# mini-v1_1.net
KiCad netlist of a schematic drawn in EAGLE
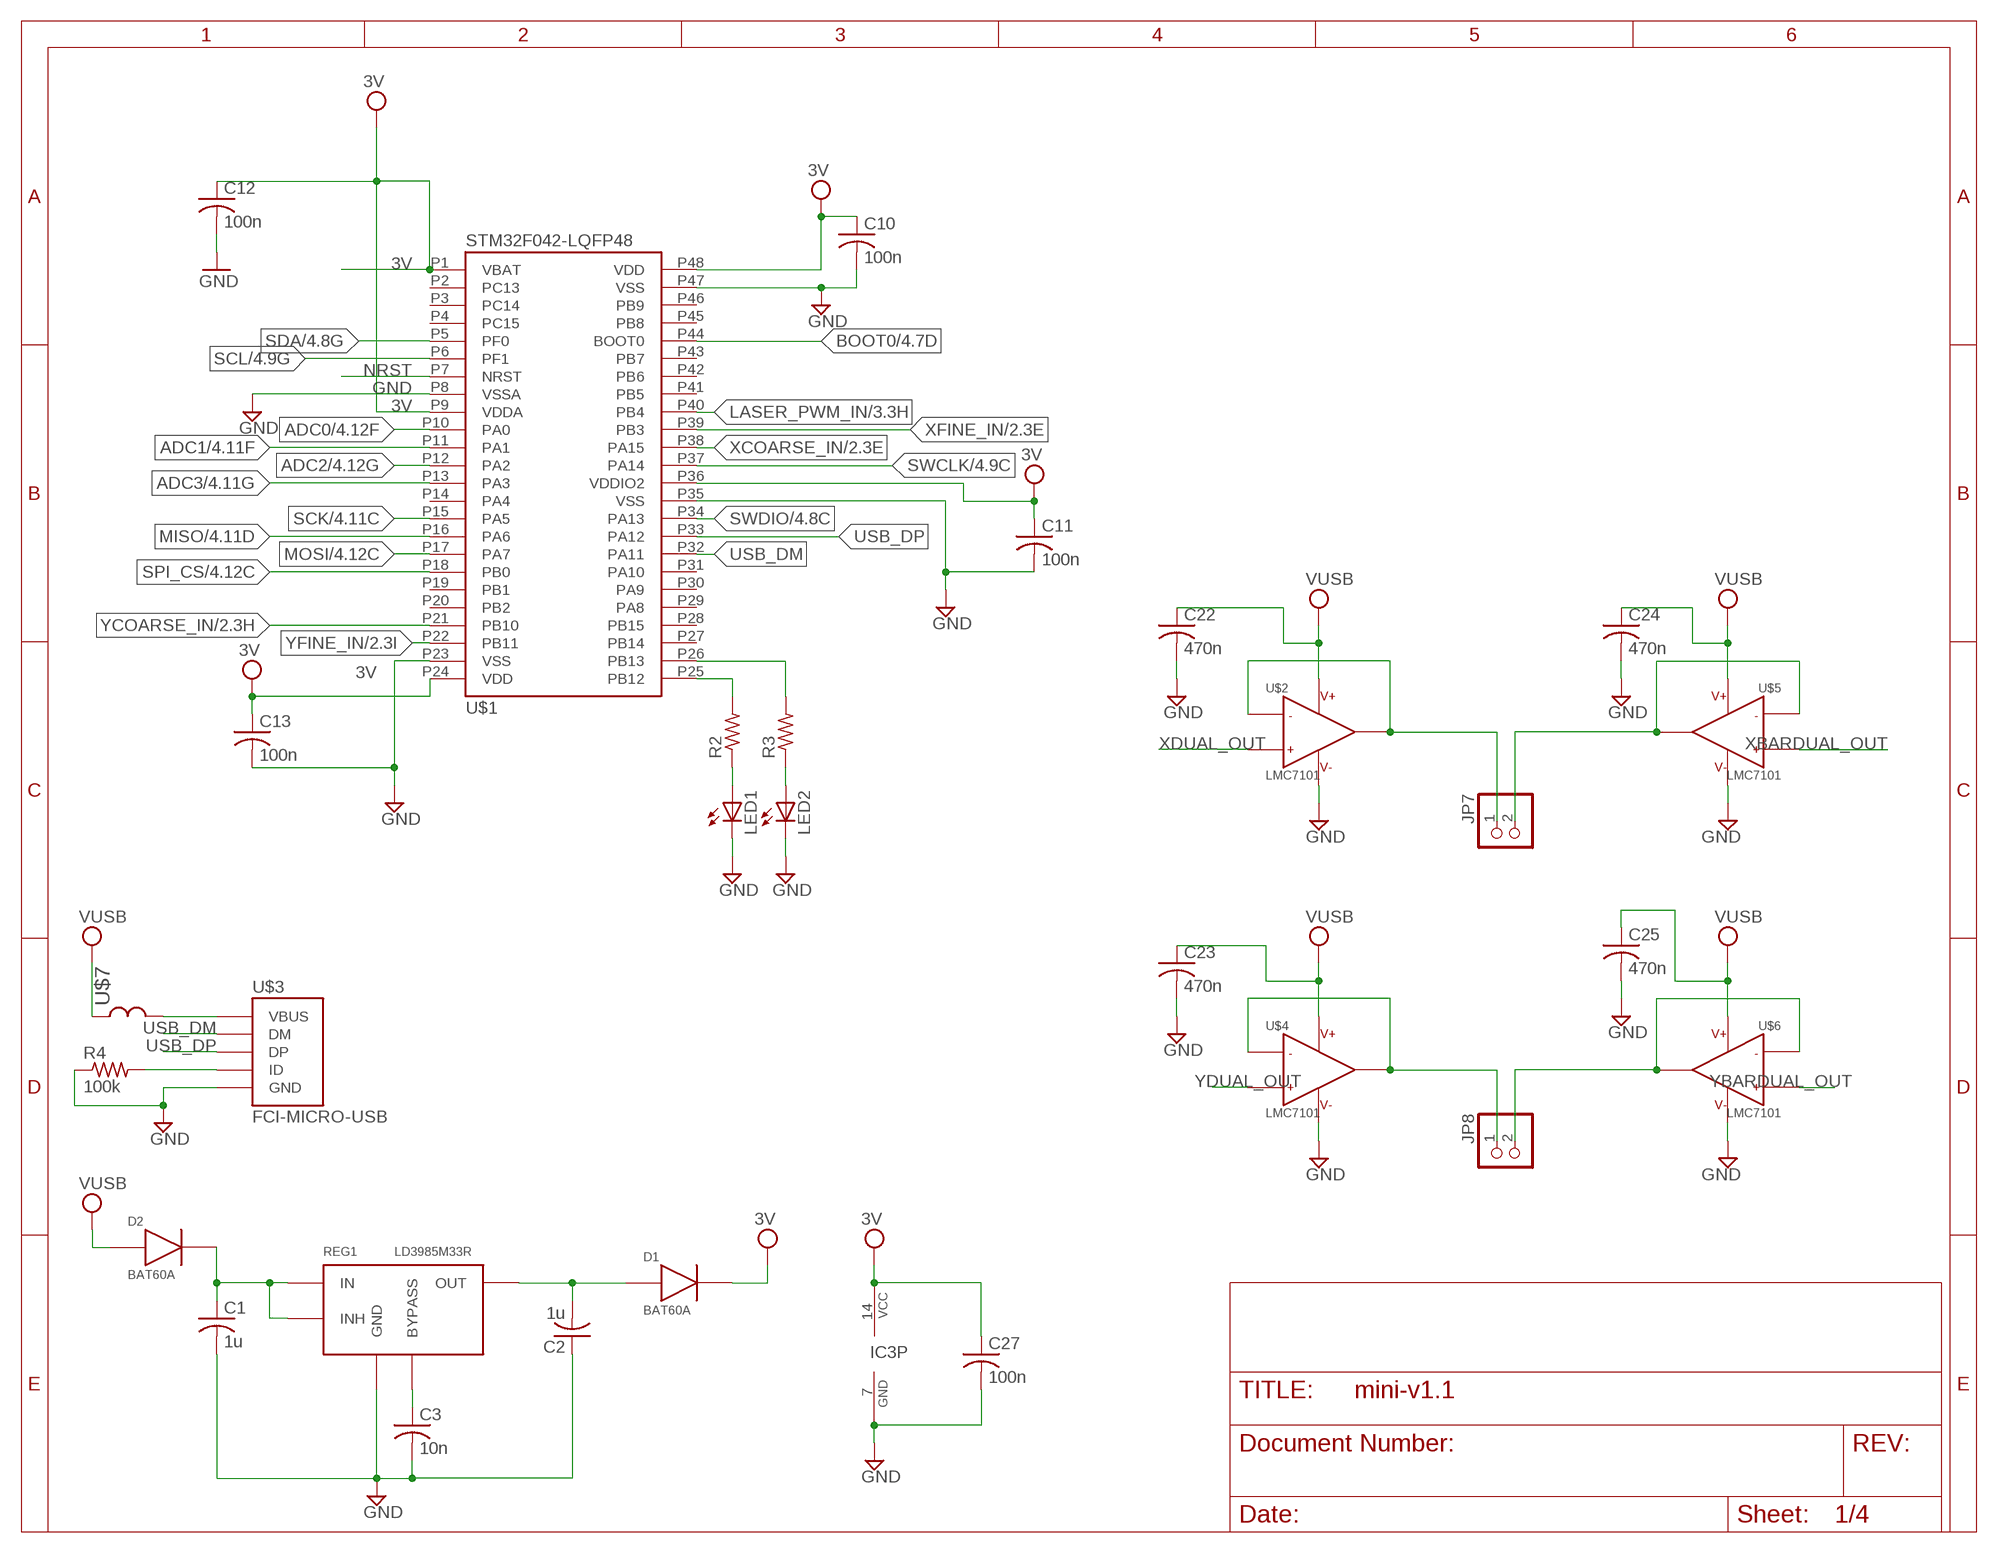
[diagram p0: schematic, sheet 1]
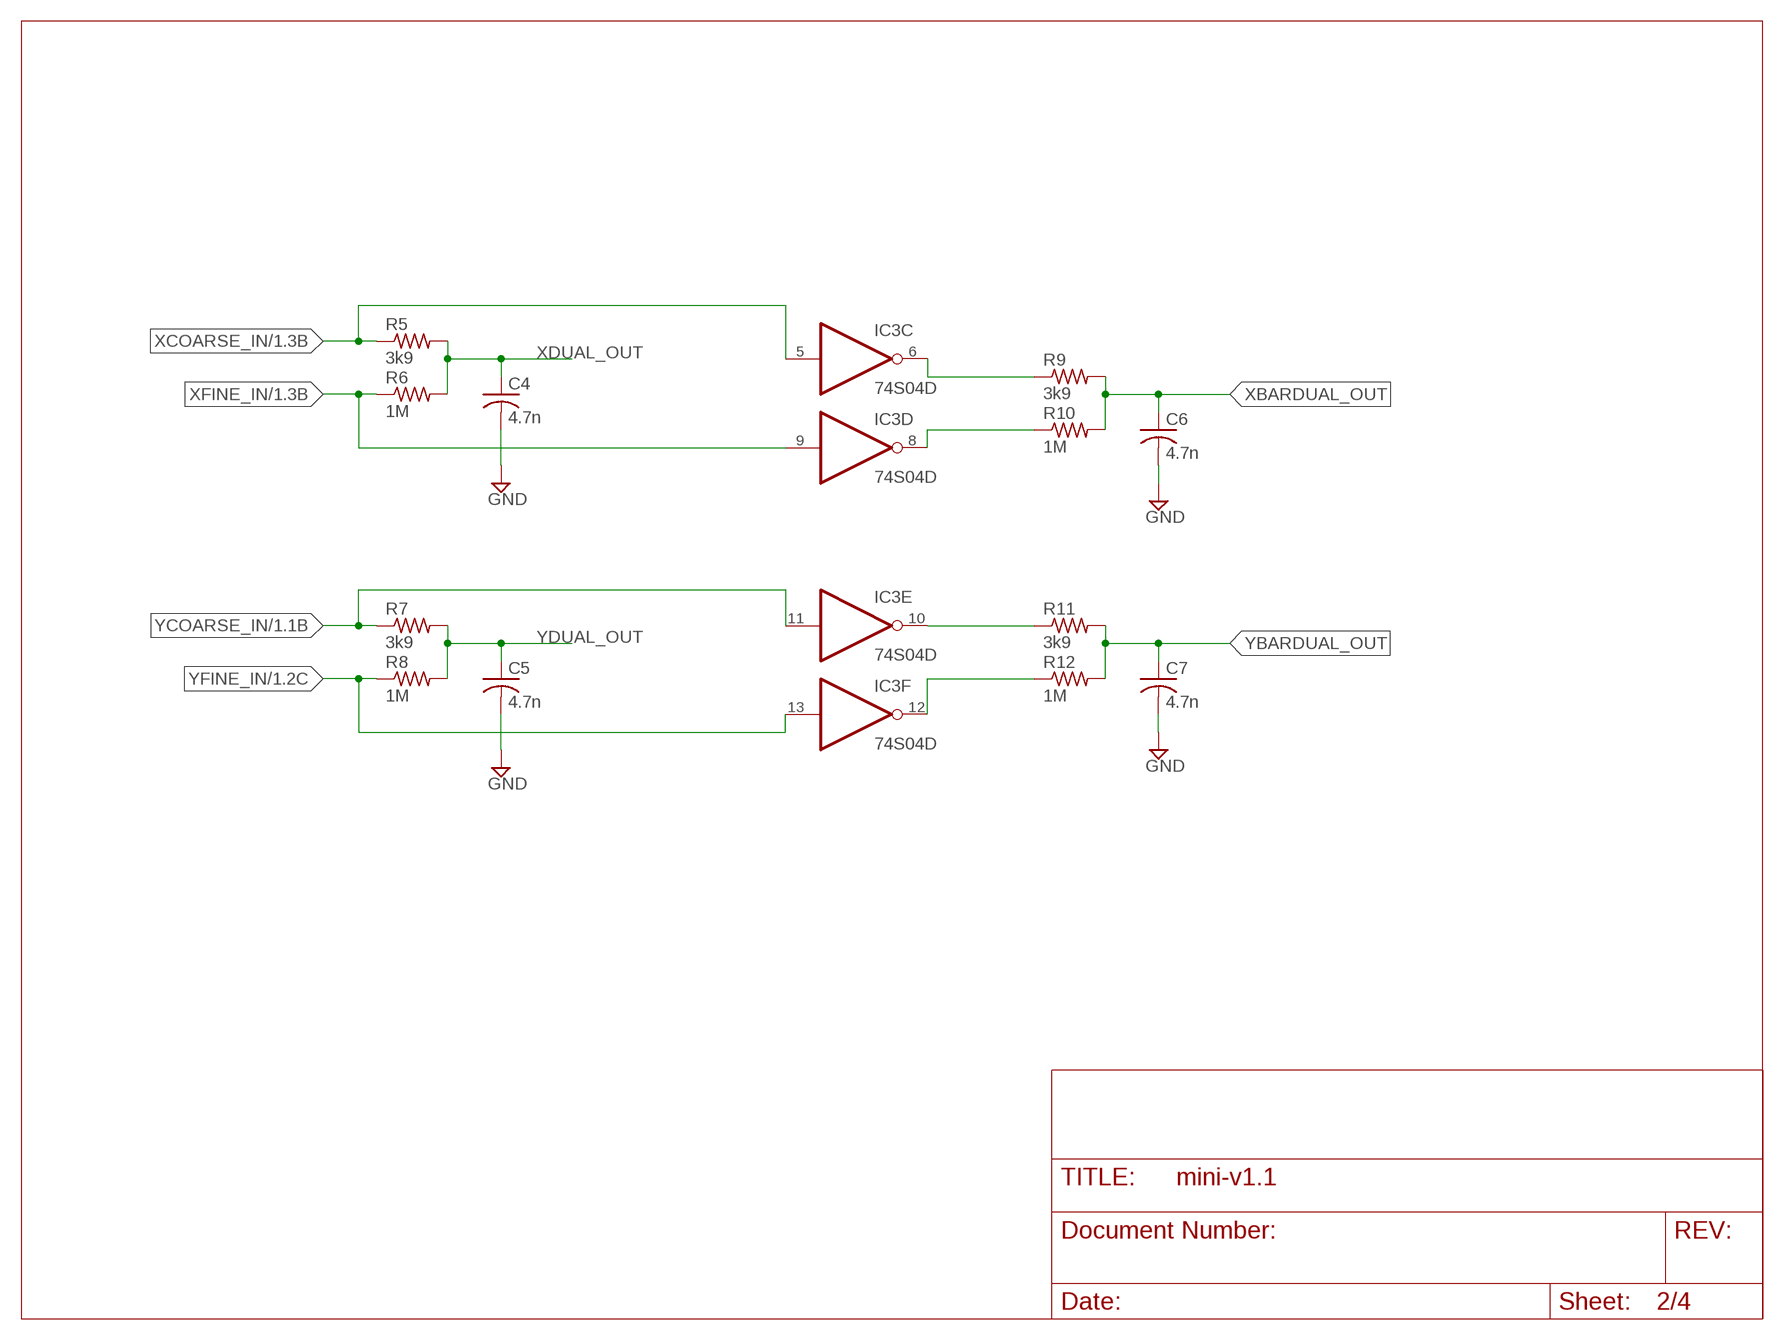
[diagram p1: schematic, sheet 2]
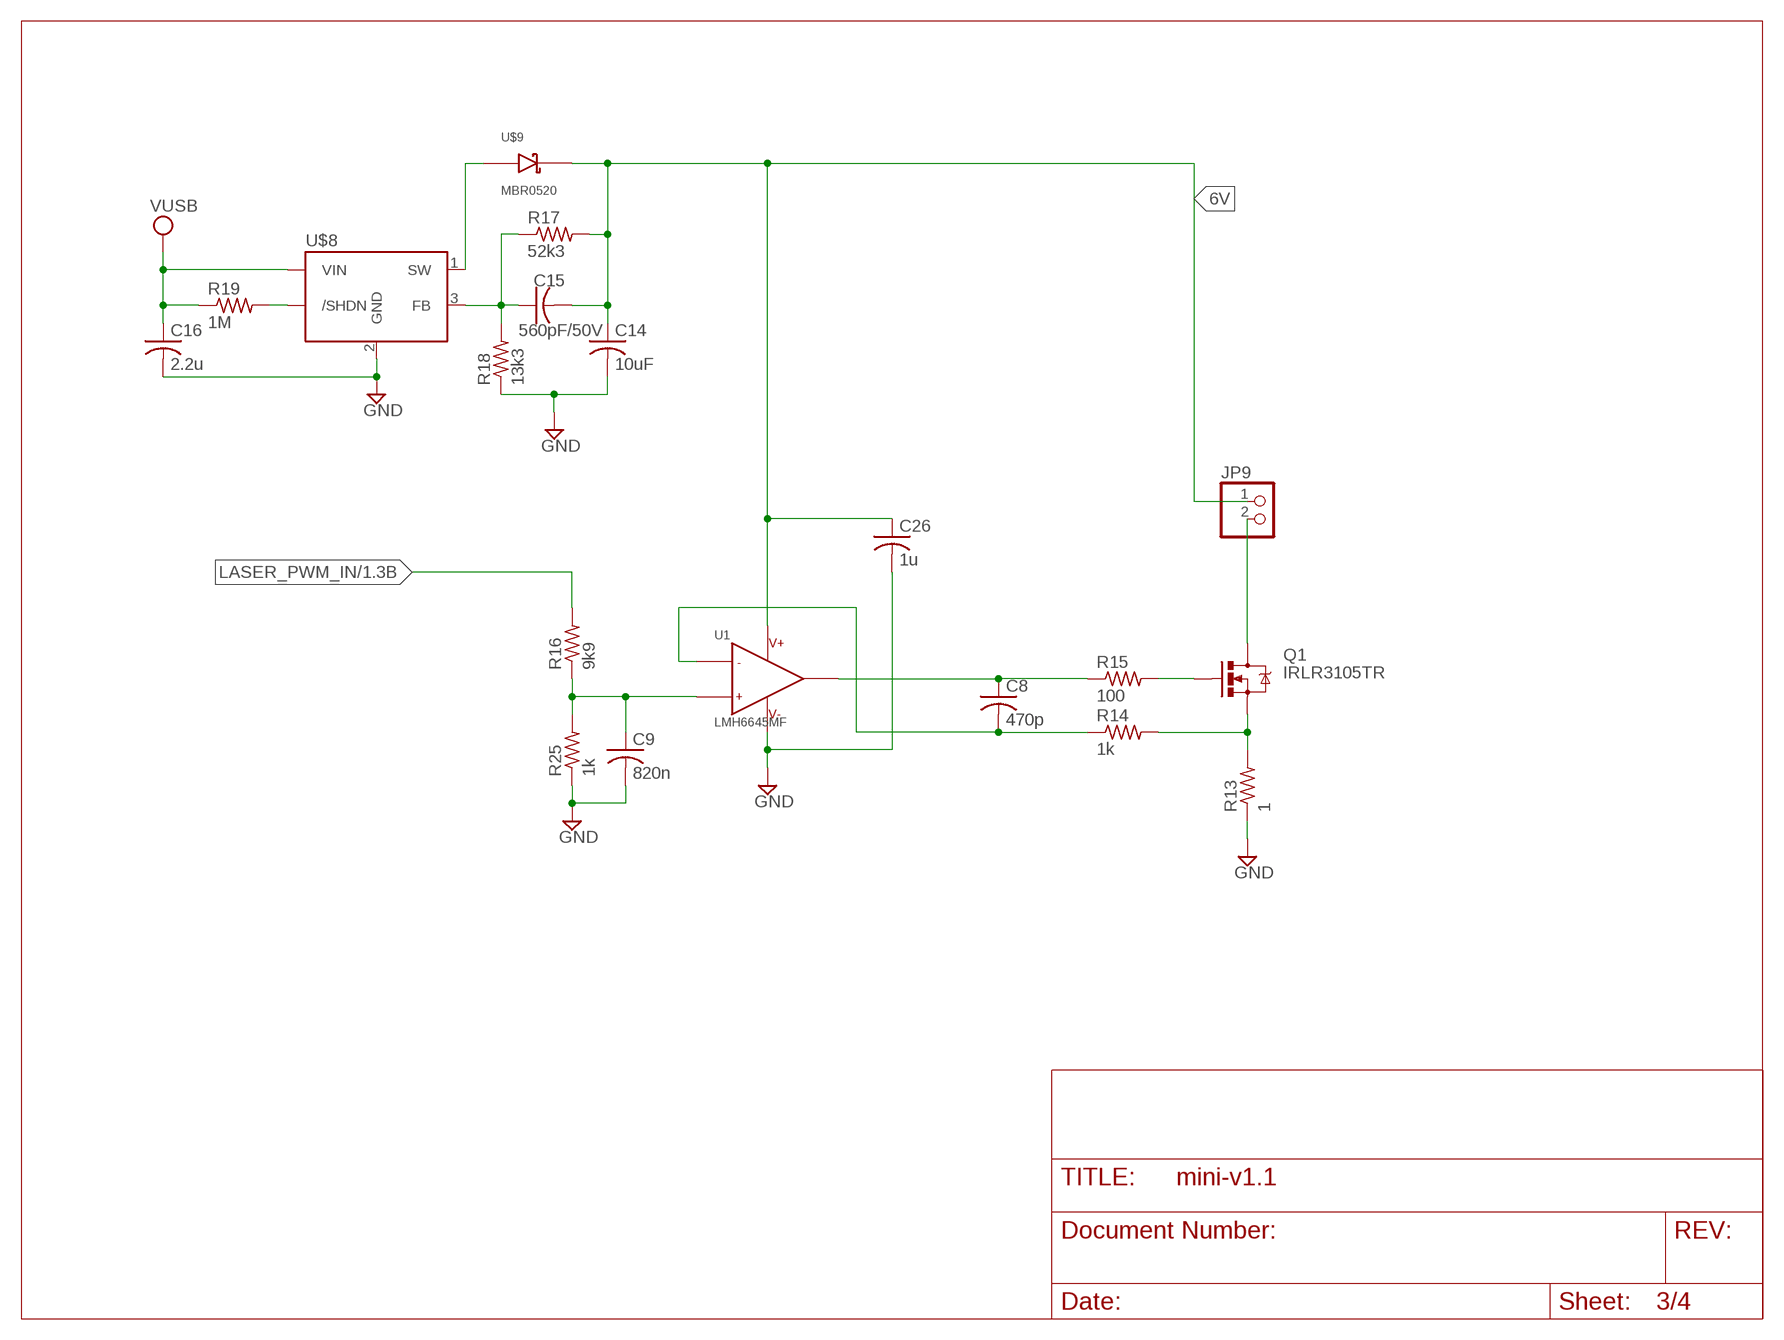
[diagram p2: schematic, sheet 3]
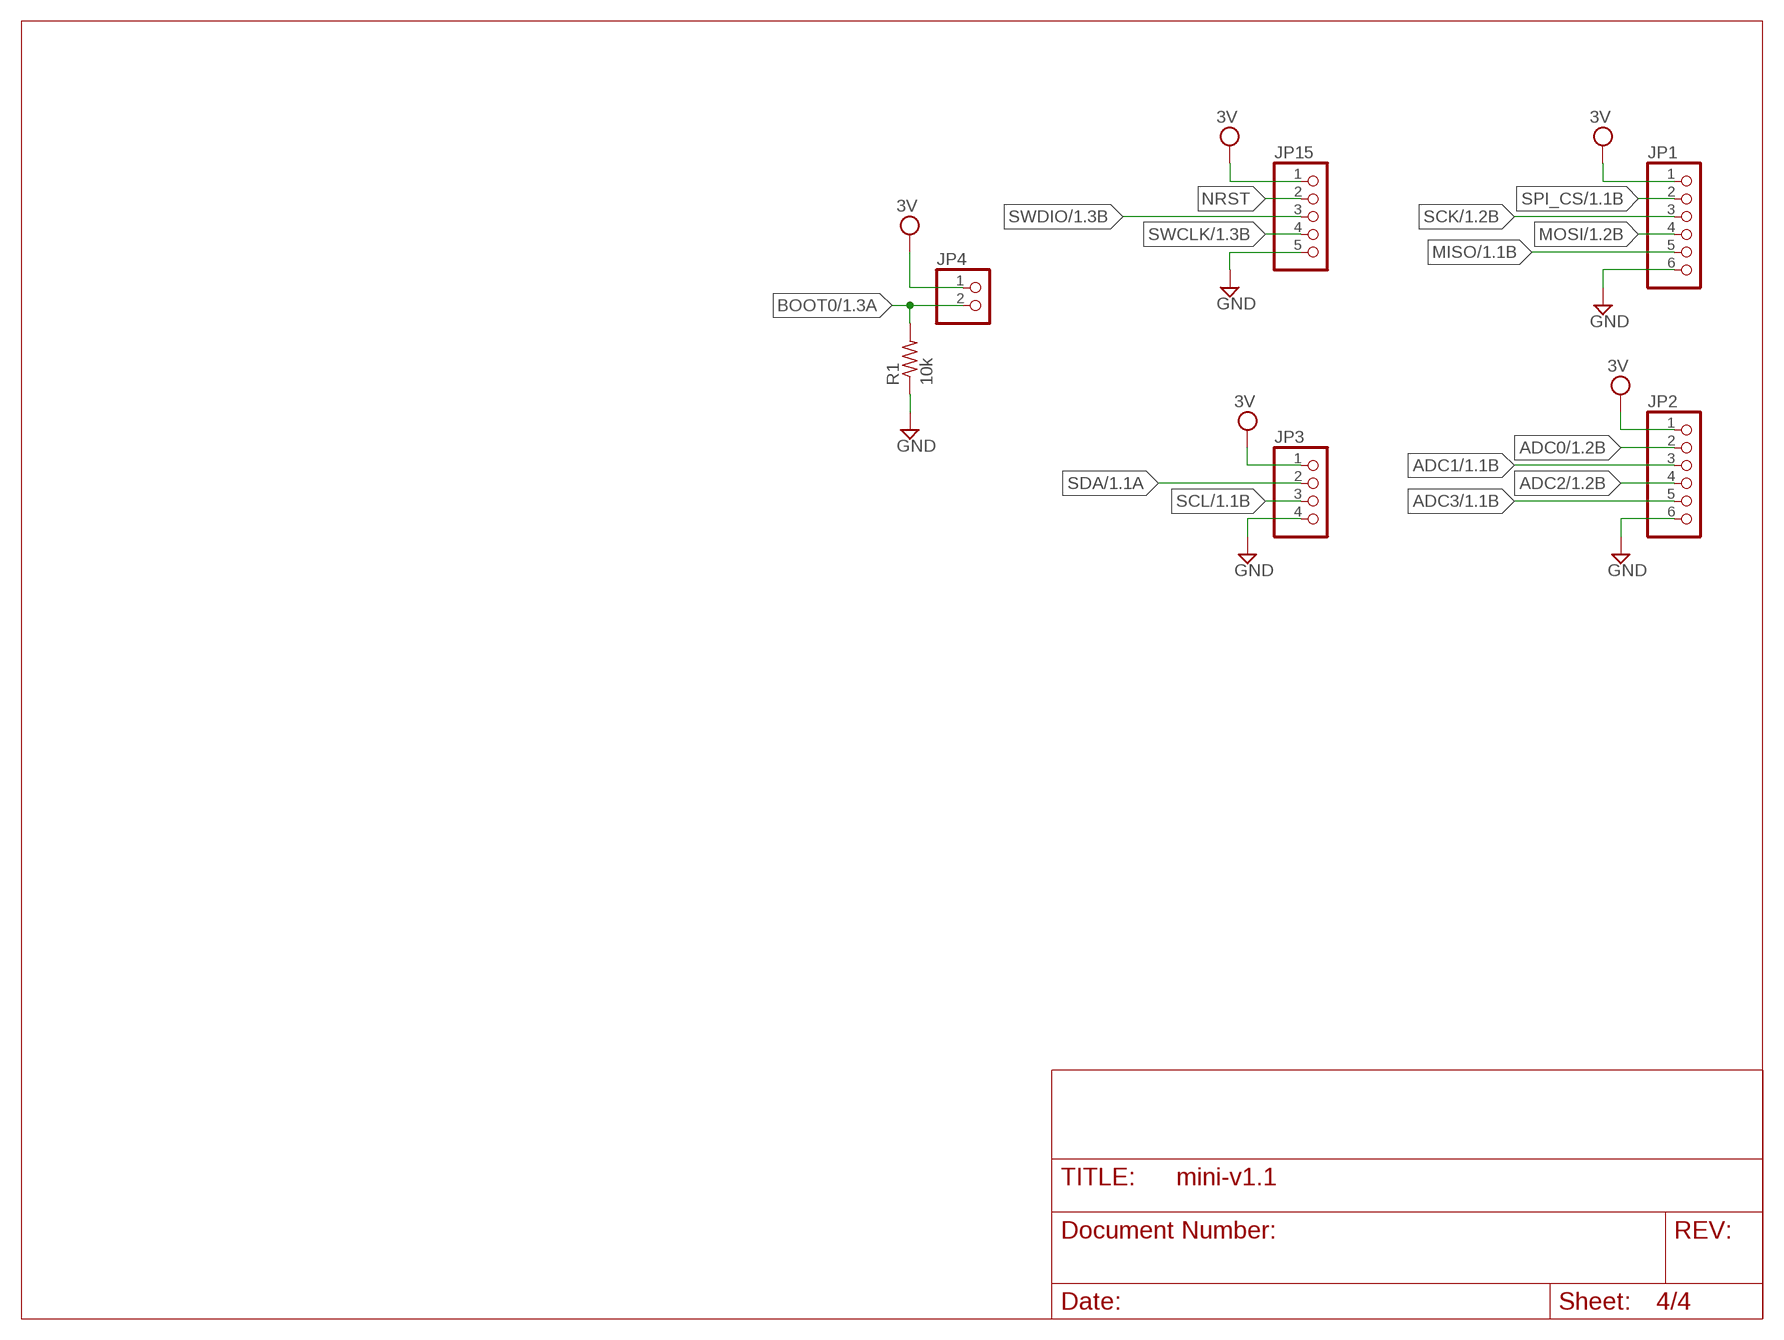
[diagram p3: schematic, sheet 4]

(export (version "E")
  (design (tool "Eeschema 10.0.6"))
  (components
    (comp (ref "C8")
      (value "470p")
      (footprint "eagle-import:C0603")
      (libsource (lib "eagle-import") (part "C-USC0603"))
    )
    (comp (ref "C9")
      (value "820n")
      (footprint "eagle-import:C0603")
      (libsource (lib "eagle-import") (part "C-USC0603"))
    )
    (comp (ref "C14")
      (value "10uF")
      (footprint "eagle-import:C0603")
      (libsource (lib "eagle-import") (part "C-USC0603"))
    )
    (comp (ref "C15")
      (value "560pF/50V")
      (footprint "eagle-import:C0603")
      (libsource (lib "eagle-import") (part "C-USC0603"))
    )
    (comp (ref "C16")
      (value "2.2u")
      (footprint "eagle-import:C0603")
      (libsource (lib "eagle-import") (part "C-USC0603"))
    )
    (comp (ref "C26")
      (value "1u")
      (footprint "eagle-import:C0603")
      (libsource (lib "eagle-import") (part "C-USC0603"))
    )
    (comp (ref "JP9")
      (value "PINHD-1X2")
      (footprint "eagle-import:1X02")
      (libsource (lib "eagle-import") (part "PINHD-1X2"))
    )
    (comp (ref "Q1")
      (value "IRLR3105TR")
      (footprint "eagle-import:DPAK")
      (libsource (lib "eagle-import") (part "FET-N-IRLR3105TRIRLR3105TR"))
    )
    (comp (ref "R13")
      (value "1")
      (footprint "eagle-import:R0603")
      (libsource (lib "eagle-import") (part "R-US_R0603"))
    )
    (comp (ref "R14")
      (value "1k")
      (footprint "eagle-import:R0603")
      (libsource (lib "eagle-import") (part "R-US_R0603"))
    )
    (comp (ref "R15")
      (value "100")
      (footprint "eagle-import:R0603")
      (libsource (lib "eagle-import") (part "R-US_R0603"))
    )
    (comp (ref "R16")
      (value "9k9")
      (footprint "eagle-import:R0603")
      (libsource (lib "eagle-import") (part "R-US_R0603"))
    )
    (comp (ref "R17")
      (value "52k3")
      (footprint "eagle-import:R0603")
      (libsource (lib "eagle-import") (part "R-US_R0603"))
    )
    (comp (ref "R18")
      (value "13k3")
      (footprint "eagle-import:R0603")
      (libsource (lib "eagle-import") (part "R-US_R0603"))
    )
    (comp (ref "R19")
      (value "1M")
      (footprint "eagle-import:R0603")
      (libsource (lib "eagle-import") (part "R-US_R0603"))
    )
    (comp (ref "R25")
      (value "1k")
      (footprint "eagle-import:R0603")
      (libsource (lib "eagle-import") (part "R-US_R0603"))
    )
    (comp (ref "U$8")
      (value "LMR62014")
      (footprint "eagle-import:SOT23-5")
      (libsource (lib "eagle-import") (part "LMR62014"))
    )
    (comp (ref "U$9")
      (value "MBR0520")
      (footprint "eagle-import:SOD123")
      (libsource (lib "eagle-import") (part "MBR0520"))
    )
    (comp (ref "U1")
      (value "LMH6645MF")
      (footprint "eagle-import:SOT23-5")
      (libsource (lib "eagle-import") (part "OPAMP-SINGLELMH6645MF"))
    )
    (comp (ref "JP1")
      (value "PINHD-1X6")
      (footprint "eagle-import:1X06")
      (libsource (lib "eagle-import") (part "PINHD-1X6"))
    )
    (comp (ref "JP2")
      (value "PINHD-1X6")
      (footprint "eagle-import:1X06")
      (libsource (lib "eagle-import") (part "PINHD-1X6"))
    )
    (comp (ref "JP3")
      (value "PINHD-1X4")
      (footprint "eagle-import:1X04")
      (libsource (lib "eagle-import") (part "PINHD-1X4"))
    )
    (comp (ref "JP4")
      (value "PINHD-1X2")
      (footprint "eagle-import:1X02")
      (libsource (lib "eagle-import") (part "PINHD-1X2"))
    )
    (comp (ref "JP15")
      (value "PINHD-1X5")
      (footprint "eagle-import:1X05")
      (libsource (lib "eagle-import") (part "PINHD-1X5"))
    )
    (comp (ref "R1")
      (value "10k")
      (footprint "eagle-import:R0603")
      (libsource (lib "eagle-import") (part "R-US_R0603"))
    )
    (comp (ref "C4")
      (value "4.7n")
      (footprint "eagle-import:C0603")
      (libsource (lib "eagle-import") (part "C-USC0603"))
    )
    (comp (ref "C5")
      (value "4.7n")
      (footprint "eagle-import:C0603")
      (libsource (lib "eagle-import") (part "C-USC0603"))
    )
    (comp (ref "C6")
      (value "4.7n")
      (footprint "eagle-import:C0603")
      (libsource (lib "eagle-import") (part "C-USC0603"))
    )
    (comp (ref "C7")
      (value "4.7n")
      (footprint "eagle-import:C0603")
      (libsource (lib "eagle-import") (part "C-USC0603"))
    )
    (comp (ref "IC3")
      (value "74S04D")
      (footprint "eagle-import:SO14")
      (libsource (lib "eagle-import") (part "7404DS"))
    )
    (comp (ref "R5")
      (value "3k9")
      (footprint "eagle-import:R0603")
      (libsource (lib "eagle-import") (part "R-US_R0603"))
    )
    (comp (ref "R6")
      (value "1M")
      (footprint "eagle-import:R0603")
      (libsource (lib "eagle-import") (part "R-US_R0603"))
    )
    (comp (ref "R7")
      (value "3k9")
      (footprint "eagle-import:R0603")
      (libsource (lib "eagle-import") (part "R-US_R0603"))
    )
    (comp (ref "R8")
      (value "1M")
      (footprint "eagle-import:R0603")
      (libsource (lib "eagle-import") (part "R-US_R0603"))
    )
    (comp (ref "R9")
      (value "3k9")
      (footprint "eagle-import:R0603")
      (libsource (lib "eagle-import") (part "R-US_R0603"))
    )
    (comp (ref "R10")
      (value "1M")
      (footprint "eagle-import:R0603")
      (libsource (lib "eagle-import") (part "R-US_R0603"))
    )
    (comp (ref "R11")
      (value "3k9")
      (footprint "eagle-import:R0603")
      (libsource (lib "eagle-import") (part "R-US_R0603"))
    )
    (comp (ref "R12")
      (value "1M")
      (footprint "eagle-import:R0603")
      (libsource (lib "eagle-import") (part "R-US_R0603"))
    )
    (comp (ref "C1")
      (value "1u")
      (footprint "eagle-import:C0603")
      (libsource (lib "eagle-import") (part "C-USC0603"))
    )
    (comp (ref "C2")
      (value "1u")
      (footprint "eagle-import:C0603")
      (libsource (lib "eagle-import") (part "C-USC0603"))
    )
    (comp (ref "C3")
      (value "10n")
      (footprint "eagle-import:C0603")
      (libsource (lib "eagle-import") (part "C-USC0603"))
    )
    (comp (ref "C10")
      (value "100n")
      (footprint "eagle-import:C0603")
      (libsource (lib "eagle-import") (part "C-USC0603"))
    )
    (comp (ref "C11")
      (value "100n")
      (footprint "eagle-import:C0603")
      (libsource (lib "eagle-import") (part "C-USC0603"))
    )
    (comp (ref "C12")
      (value "100n")
      (footprint "eagle-import:C0603")
      (libsource (lib "eagle-import") (part "C-USC0603"))
    )
    (comp (ref "C13")
      (value "100n")
      (footprint "eagle-import:C0603")
      (libsource (lib "eagle-import") (part "C-USC0603"))
    )
    (comp (ref "C22")
      (value "470n")
      (footprint "eagle-import:C0603")
      (libsource (lib "eagle-import") (part "C-USC0603"))
    )
    (comp (ref "C23")
      (value "470n")
      (footprint "eagle-import:C0603")
      (libsource (lib "eagle-import") (part "C-USC0603"))
    )
    (comp (ref "C24")
      (value "470n")
      (footprint "eagle-import:C0603")
      (libsource (lib "eagle-import") (part "C-USC0603"))
    )
    (comp (ref "C25")
      (value "470n")
      (footprint "eagle-import:C0603")
      (libsource (lib "eagle-import") (part "C-USC0603"))
    )
    (comp (ref "C27")
      (value "100n")
      (footprint "eagle-import:C0603")
      (libsource (lib "eagle-import") (part "C-USC0603"))
    )
    (comp (ref "D1")
      (value "BAT60A")
      (footprint "eagle-import:SOD323")
      (libsource (lib "eagle-import") (part "BAT60A"))
    )
    (comp (ref "D2")
      (value "BAT60A")
      (footprint "eagle-import:SOD323")
      (libsource (lib "eagle-import") (part "BAT60A"))
    )
    (comp (ref "JP7")
      (value "PINHD-1X2")
      (footprint "eagle-import:1X02")
      (libsource (lib "eagle-import") (part "PINHD-1X2"))
    )
    (comp (ref "JP8")
      (value "PINHD-1X2")
      (footprint "eagle-import:1X02")
      (libsource (lib "eagle-import") (part "PINHD-1X2"))
    )
    (comp (ref "LED1")
      (value "LED")
      (footprint "eagle-import:SMARTLED-TTW")
      (libsource (lib "eagle-import") (part "LED"))
    )
    (comp (ref "LED2")
      (value "LED")
      (footprint "eagle-import:SMARTLED-TTW")
      (libsource (lib "eagle-import") (part "LED"))
    )
    (comp (ref "R2")
      (value "R-US_R0603")
      (footprint "eagle-import:R0603")
      (libsource (lib "eagle-import") (part "R-US_R0603"))
    )
    (comp (ref "R3")
      (value "R-US_R0603")
      (footprint "eagle-import:R0603")
      (libsource (lib "eagle-import") (part "R-US_R0603"))
    )
    (comp (ref "R4")
      (value "100k")
      (footprint "eagle-import:R0603")
      (libsource (lib "eagle-import") (part "R-US_R0603"))
    )
    (comp (ref "REG1")
      (value "LD3985M33R")
      (footprint "eagle-import:SOT23-5L")
      (libsource (lib "eagle-import") (part "LD3985MXXR"))
    )
    (comp (ref "U$1")
      (value "STM32F042-LQFP48")
      (footprint "eagle-import:LQFP48")
      (libsource (lib "eagle-import") (part "STM32F042-LQFP48"))
    )
    (comp (ref "U$2")
      (value "LMC7101")
      (footprint "eagle-import:SOT23-5")
      (libsource (lib "eagle-import") (part "LMC7101"))
    )
    (comp (ref "U$3")
      (value "FCI-MICRO-USB")
      (footprint "eagle-import:FCI-MICROUSB")
      (libsource (lib "eagle-import") (part "FCI-MICRO-USB"))
    )
    (comp (ref "U$4")
      (value "LMC7101")
      (footprint "eagle-import:SOT23-5")
      (libsource (lib "eagle-import") (part "LMC7101"))
    )
    (comp (ref "U$5")
      (value "LMC7101")
      (footprint "eagle-import:SOT23-5")
      (libsource (lib "eagle-import") (part "LMC7101"))
    )
    (comp (ref "U$6")
      (value "LMC7101")
      (footprint "eagle-import:SOT23-5")
      (libsource (lib "eagle-import") (part "LMC7101"))
    )
    (comp (ref "U$7")
      (value "L_TDK_1005")
      (footprint "eagle-import:MLK1005")
      (libsource (lib "eagle-import") (part "L_TDK_1005"))
    )
  )
  (nets
    (net (code "1") (name "3V") (class "Default")
      (node (ref "C10") (pin "1") (pinfunction "1_1") (pintype "passive"))
      (node (ref "C11") (pin "1") (pinfunction "1_1") (pintype "passive"))
      (node (ref "C12") (pin "1") (pinfunction "1_1") (pintype "passive"))
      (node (ref "C13") (pin "1") (pinfunction "1_1") (pintype "passive"))
      (node (ref "C27") (pin "1") (pinfunction "1_1") (pintype "passive"))
      (node (ref "D1") (pin "1") (pinfunction "1_1") (pintype "bidirectional"))
      (node (ref "IC3") (pin "14") (pinfunction "VCC_14") (pintype "power_in"))
      (node (ref "JP1") (pin "1") (pinfunction "1_1") (pintype "passive"))
      (node (ref "JP15") (pin "1") (pinfunction "1_1") (pintype "passive"))
      (node (ref "JP2") (pin "1") (pinfunction "1_1") (pintype "passive"))
      (node (ref "JP3") (pin "1") (pinfunction "1_1") (pintype "passive"))
      (node (ref "JP4") (pin "1") (pinfunction "1_1") (pintype "passive"))
      (node (ref "U$1") (pin "P1") (pinfunction "VBAT_P1") (pintype "bidirectional"))
      (node (ref "U$1") (pin "P24") (pinfunction "VDD_P24") (pintype "bidirectional"))
      (node (ref "U$1") (pin "P36") (pinfunction "VDDIO2_P36") (pintype "bidirectional"))
      (node (ref "U$1") (pin "P48") (pinfunction "VDD_P48") (pintype "bidirectional"))
      (node (ref "U$1") (pin "P9") (pinfunction "VDDA_P9") (pintype "bidirectional"))
    )
    (net (code "2") (name "6V") (class "Default")
      (node (ref "C14") (pin "1") (pinfunction "1_1") (pintype "passive"))
      (node (ref "C15") (pin "2") (pinfunction "2_2") (pintype "passive"))
      (node (ref "C26") (pin "1") (pinfunction "1_1") (pintype "passive"))
      (node (ref "JP9") (pin "1") (pinfunction "1_1") (pintype "passive"))
      (node (ref "R17") (pin "2") (pinfunction "2_2") (pintype "passive"))
      (node (ref "U$9") (pin "CATHODE") (pinfunction "CATHODE_CATHODE") (pintype "bidirectional"))
      (node (ref "U1") (pin "5") (pinfunction "V+_5") (pintype "power_in"))
    )
    (net (code "3") (name "ADC0") (class "Default")
      (node (ref "JP2") (pin "2") (pinfunction "2_2") (pintype "passive"))
      (node (ref "U$1") (pin "P10") (pinfunction "PA0_P10") (pintype "bidirectional"))
    )
    (net (code "4") (name "ADC1") (class "Default")
      (node (ref "JP2") (pin "3") (pinfunction "3_3") (pintype "passive"))
      (node (ref "U$1") (pin "P11") (pinfunction "PA1_P11") (pintype "bidirectional"))
    )
    (net (code "5") (name "ADC2") (class "Default")
      (node (ref "JP2") (pin "4") (pinfunction "4_4") (pintype "passive"))
      (node (ref "U$1") (pin "P12") (pinfunction "PA2_P12") (pintype "bidirectional"))
    )
    (net (code "6") (name "ADC3") (class "Default")
      (node (ref "JP2") (pin "5") (pinfunction "5_5") (pintype "passive"))
      (node (ref "U$1") (pin "P13") (pinfunction "PA3_P13") (pintype "bidirectional"))
    )
    (net (code "7") (name "BOOT0") (class "Default")
      (node (ref "JP4") (pin "2") (pinfunction "2_2") (pintype "passive"))
      (node (ref "R1") (pin "2") (pinfunction "2_2") (pintype "passive"))
      (node (ref "U$1") (pin "P44") (pinfunction "BOOT0_P44") (pintype "bidirectional"))
    )
    (net (code "8") (name "GND") (class "Default")
      (node (ref "C1") (pin "2") (pinfunction "2_2") (pintype "passive"))
      (node (ref "C10") (pin "2") (pinfunction "2_2") (pintype "passive"))
      (node (ref "C11") (pin "2") (pinfunction "2_2") (pintype "passive"))
      (node (ref "C12") (pin "2") (pinfunction "2_2") (pintype "passive"))
      (node (ref "C13") (pin "2") (pinfunction "2_2") (pintype "passive"))
      (node (ref "C14") (pin "2") (pinfunction "2_2") (pintype "passive"))
      (node (ref "C16") (pin "2") (pinfunction "2_2") (pintype "passive"))
      (node (ref "C2") (pin "1") (pinfunction "1_1") (pintype "passive"))
      (node (ref "C22") (pin "2") (pinfunction "2_2") (pintype "passive"))
      (node (ref "C23") (pin "2") (pinfunction "2_2") (pintype "passive"))
      (node (ref "C24") (pin "2") (pinfunction "2_2") (pintype "passive"))
      (node (ref "C25") (pin "2") (pinfunction "2_2") (pintype "passive"))
      (node (ref "C26") (pin "2") (pinfunction "2_2") (pintype "passive"))
      (node (ref "C27") (pin "2") (pinfunction "2_2") (pintype "passive"))
      (node (ref "C3") (pin "2") (pinfunction "2_2") (pintype "passive"))
      (node (ref "C4") (pin "2") (pinfunction "2_2") (pintype "passive"))
      (node (ref "C5") (pin "2") (pinfunction "2_2") (pintype "passive"))
      (node (ref "C6") (pin "2") (pinfunction "2_2") (pintype "passive"))
      (node (ref "C7") (pin "2") (pinfunction "2_2") (pintype "passive"))
      (node (ref "C9") (pin "2") (pinfunction "2_2") (pintype "passive"))
      (node (ref "IC3") (pin "7") (pinfunction "GND_7") (pintype "power_in"))
      (node (ref "JP1") (pin "6") (pinfunction "6_6") (pintype "passive"))
      (node (ref "JP15") (pin "5") (pinfunction "5_5") (pintype "passive"))
      (node (ref "JP2") (pin "6") (pinfunction "6_6") (pintype "passive"))
      (node (ref "JP3") (pin "4") (pinfunction "4_4") (pintype "passive"))
      (node (ref "LED1") (pin "C@1") (pinfunction "C_C@1") (pintype "passive"))
      (node (ref "LED2") (pin "C@1") (pinfunction "C_C@1") (pintype "passive"))
      (node (ref "R1") (pin "1") (pinfunction "1_1") (pintype "passive"))
      (node (ref "R13") (pin "1") (pinfunction "1_1") (pintype "passive"))
      (node (ref "R18") (pin "1") (pinfunction "1_1") (pintype "passive"))
      (node (ref "R25") (pin "1") (pinfunction "1_1") (pintype "passive"))
      (node (ref "R4") (pin "1") (pinfunction "1_1") (pintype "passive"))
      (node (ref "REG1") (pin "GND") (pinfunction "GND_GND") (pintype "bidirectional"))
      (node (ref "U$1") (pin "P23") (pinfunction "VSS_P23") (pintype "bidirectional"))
      (node (ref "U$1") (pin "P35") (pinfunction "VSS_P35") (pintype "bidirectional"))
      (node (ref "U$1") (pin "P47") (pinfunction "VSS_P47") (pintype "bidirectional"))
      (node (ref "U$1") (pin "P8") (pinfunction "VSSA_P8") (pintype "bidirectional"))
      (node (ref "U$2") (pin "5") (pinfunction "P5_5") (pintype "power_in"))
      (node (ref "U$3") (pin "P5") (pinfunction "GND_P5") (pintype "bidirectional"))
      (node (ref "U$4") (pin "5") (pinfunction "P5_5") (pintype "power_in"))
      (node (ref "U$5") (pin "5") (pinfunction "P5_5") (pintype "power_in"))
      (node (ref "U$6") (pin "5") (pinfunction "P5_5") (pintype "power_in"))
      (node (ref "U$8") (pin "2") (pinfunction "GND_2") (pintype "bidirectional"))
      (node (ref "U1") (pin "2") (pinfunction "V-_2") (pintype "power_in"))
    )
    (net (code "9") (name "LASER_PWM_IN") (class "Default")
      (node (ref "R16") (pin "2") (pinfunction "2_2") (pintype "passive"))
      (node (ref "U$1") (pin "P40") (pinfunction "PB4_P40") (pintype "bidirectional"))
    )
    (net (code "10") (name "MISO") (class "Default")
      (node (ref "JP1") (pin "5") (pinfunction "5_5") (pintype "passive"))
      (node (ref "U$1") (pin "P16") (pinfunction "PA6_P16") (pintype "bidirectional"))
    )
    (net (code "11") (name "MOSI") (class "Default")
      (node (ref "JP1") (pin "4") (pinfunction "4_4") (pintype "passive"))
      (node (ref "U$1") (pin "P17") (pinfunction "PA7_P17") (pintype "bidirectional"))
    )
    (net (code "12") (name "NRST") (class "Default")
      (node (ref "JP15") (pin "2") (pinfunction "2_2") (pintype "passive"))
      (node (ref "U$1") (pin "P7") (pinfunction "NRST_P7") (pintype "bidirectional"))
    )
    (net (code "13") (name "Net-(C2-Pad2)") (class "Default")
      (node (ref "C2") (pin "2") (pinfunction "2_2") (pintype "passive"))
      (node (ref "D1") (pin "2") (pinfunction "2_2") (pintype "bidirectional"))
      (node (ref "REG1") (pin "OUT") (pinfunction "OUT_OUT") (pintype "bidirectional"))
    )
    (net (code "14") (name "Net-(C3-Pad1)") (class "Default")
      (node (ref "C3") (pin "1") (pinfunction "1_1") (pintype "passive"))
      (node (ref "REG1") (pin "BYPASS") (pinfunction "BYPASS_BYPASS") (pintype "bidirectional"))
    )
    (net (code "15") (name "Net-(IC3C-O)") (class "Default")
      (node (ref "IC3") (pin "6") (pinfunction "O_6") (pintype "output"))
      (node (ref "R9") (pin "1") (pinfunction "1_1") (pintype "passive"))
    )
    (net (code "16") (name "Net-(IC3D-O)") (class "Default")
      (node (ref "IC3") (pin "8") (pinfunction "O_8") (pintype "output"))
      (node (ref "R10") (pin "1") (pinfunction "1_1") (pintype "passive"))
    )
    (net (code "17") (name "Net-(IC3E-O)") (class "Default")
      (node (ref "IC3") (pin "10") (pinfunction "O_10") (pintype "output"))
      (node (ref "R11") (pin "1") (pinfunction "1_1") (pintype "passive"))
    )
    (net (code "18") (name "Net-(IC3F-O)") (class "Default")
      (node (ref "IC3") (pin "12") (pinfunction "O_12") (pintype "output"))
      (node (ref "R12") (pin "1") (pinfunction "1_1") (pintype "passive"))
    )
    (net (code "19") (name "Net-(LED1-A)") (class "Default")
      (node (ref "LED1") (pin "A@1") (pinfunction "A_A@1") (pintype "passive"))
      (node (ref "R2") (pin "1") (pinfunction "1_1") (pintype "passive"))
    )
    (net (code "20") (name "Net-(LED2-A)") (class "Default")
      (node (ref "LED2") (pin "A@1") (pinfunction "A_A@1") (pintype "passive"))
      (node (ref "R3") (pin "1") (pinfunction "1_1") (pintype "passive"))
    )
    (net (code "21") (name "Net-(Q1-D)") (class "Default")
      (node (ref "JP9") (pin "2") (pinfunction "2_2") (pintype "passive"))
      (node (ref "Q1") (pin "4") (pinfunction "D_4") (pintype "passive"))
    )
    (net (code "22") (name "Net-(Q1-G)") (class "Default")
      (node (ref "Q1") (pin "1") (pinfunction "G_1") (pintype "passive"))
      (node (ref "R15") (pin "2") (pinfunction "2_2") (pintype "passive"))
    )
    (net (code "23") (name "Net-(Q1-S)") (class "Default")
      (node (ref "Q1") (pin "3") (pinfunction "S_3") (pintype "passive"))
      (node (ref "R13") (pin "2") (pinfunction "2_2") (pintype "passive"))
      (node (ref "R14") (pin "2") (pinfunction "2_2") (pintype "passive"))
    )
    (net (code "24") (name "Net-(REG1-INH)") (class "Default")
      (node (ref "C1") (pin "1") (pinfunction "1_1") (pintype "passive"))
      (node (ref "D2") (pin "1") (pinfunction "1_1") (pintype "bidirectional"))
      (node (ref "REG1") (pin "IN") (pinfunction "IN_IN") (pintype "bidirectional"))
      (node (ref "REG1") (pin "INHIBIT") (pinfunction "INH_INHIBIT") (pintype "bidirectional"))
    )
    (net (code "25") (name "Net-(U$1-PB12)") (class "Default")
      (node (ref "R2") (pin "2") (pinfunction "2_2") (pintype "passive"))
      (node (ref "U$1") (pin "P25") (pinfunction "PB12_P25") (pintype "bidirectional"))
    )
    (net (code "26") (name "Net-(U$1-PB13)") (class "Default")
      (node (ref "R3") (pin "2") (pinfunction "2_2") (pintype "passive"))
      (node (ref "U$1") (pin "P26") (pinfunction "PB13_P26") (pintype "bidirectional"))
    )
    (net (code "27") (name "Net-(U$2-P1)") (class "Default")
      (node (ref "JP7") (pin "1") (pinfunction "1_1") (pintype "passive"))
      (node (ref "U$2") (pin "1") (pinfunction "P1_1") (pintype "bidirectional"))
      (node (ref "U$2") (pin "4") (pinfunction "P4_4") (pintype "bidirectional"))
    )
    (net (code "28") (name "Net-(U$3-ID)") (class "Default")
      (node (ref "R4") (pin "2") (pinfunction "2_2") (pintype "passive"))
      (node (ref "U$3") (pin "P4") (pinfunction "ID_P4") (pintype "bidirectional"))
    )
    (net (code "29") (name "Net-(U$3-VBUS)") (class "Default")
      (node (ref "U$3") (pin "P1") (pinfunction "VBUS_P1") (pintype "bidirectional"))
      (node (ref "U$7") (pin "P$2") (pinfunction "P$2_P$2") (pintype "bidirectional"))
    )
    (net (code "30") (name "Net-(U$4-P1)") (class "Default")
      (node (ref "JP8") (pin "1") (pinfunction "1_1") (pintype "passive"))
      (node (ref "U$4") (pin "1") (pinfunction "P1_1") (pintype "bidirectional"))
      (node (ref "U$4") (pin "4") (pinfunction "P4_4") (pintype "bidirectional"))
    )
    (net (code "31") (name "Net-(U$5-P1)") (class "Default")
      (node (ref "JP7") (pin "2") (pinfunction "2_2") (pintype "passive"))
      (node (ref "U$5") (pin "1") (pinfunction "P1_1") (pintype "bidirectional"))
      (node (ref "U$5") (pin "4") (pinfunction "P4_4") (pintype "bidirectional"))
    )
    (net (code "32") (name "Net-(U$6-P1)") (class "Default")
      (node (ref "JP8") (pin "2") (pinfunction "2_2") (pintype "passive"))
      (node (ref "U$6") (pin "1") (pinfunction "P1_1") (pintype "bidirectional"))
      (node (ref "U$6") (pin "4") (pinfunction "P4_4") (pintype "bidirectional"))
    )
    (net (code "33") (name "Net-(U$8-FB)") (class "Default")
      (node (ref "C15") (pin "1") (pinfunction "1_1") (pintype "passive"))
      (node (ref "R17") (pin "1") (pinfunction "1_1") (pintype "passive"))
      (node (ref "R18") (pin "2") (pinfunction "2_2") (pintype "passive"))
      (node (ref "U$8") (pin "3") (pinfunction "FB_3") (pintype "bidirectional"))
    )
    (net (code "34") (name "Net-(U$8-SW)") (class "Default")
      (node (ref "U$8") (pin "1") (pinfunction "SW_1") (pintype "bidirectional"))
      (node (ref "U$9") (pin "ANODE") (pinfunction "ANODE_ANODE") (pintype "bidirectional"))
    )
    (net (code "35") (name "Net-(U$8-{slash}SHDN)") (class "Default")
      (node (ref "R19") (pin "2") (pinfunction "2_2") (pintype "passive"))
      (node (ref "U$8") (pin "4") (pinfunction "/SHDN_4") (pintype "bidirectional"))
    )
    (net (code "36") (name "Net-(U1-IN+)") (class "Default")
      (node (ref "C9") (pin "1") (pinfunction "1_1") (pintype "passive"))
      (node (ref "R16") (pin "1") (pinfunction "1_1") (pintype "passive"))
      (node (ref "R25") (pin "2") (pinfunction "2_2") (pintype "passive"))
      (node (ref "U1") (pin "3") (pinfunction "IN+_3") (pintype "bidirectional"))
    )
    (net (code "37") (name "Net-(U1-IN-)") (class "Default")
      (node (ref "C8") (pin "2") (pinfunction "2_2") (pintype "passive"))
      (node (ref "R14") (pin "1") (pinfunction "1_1") (pintype "passive"))
      (node (ref "U1") (pin "4") (pinfunction "IN-_4") (pintype "bidirectional"))
    )
    (net (code "38") (name "Net-(U1-OUT)") (class "Default")
      (node (ref "C8") (pin "1") (pinfunction "1_1") (pintype "passive"))
      (node (ref "R15") (pin "1") (pinfunction "1_1") (pintype "passive"))
      (node (ref "U1") (pin "1") (pinfunction "OUT_1") (pintype "bidirectional"))
    )
    (net (code "39") (name "SCK") (class "Default")
      (node (ref "JP1") (pin "3") (pinfunction "3_3") (pintype "passive"))
      (node (ref "U$1") (pin "P15") (pinfunction "PA5_P15") (pintype "bidirectional"))
    )
    (net (code "40") (name "SCL") (class "Default")
      (node (ref "JP3") (pin "3") (pinfunction "3_3") (pintype "passive"))
      (node (ref "U$1") (pin "P6") (pinfunction "PF1_P6") (pintype "bidirectional"))
    )
    (net (code "41") (name "SDA") (class "Default")
      (node (ref "JP3") (pin "2") (pinfunction "2_2") (pintype "passive"))
      (node (ref "U$1") (pin "P5") (pinfunction "PF0_P5") (pintype "bidirectional"))
    )
    (net (code "42") (name "SPI_CS") (class "Default")
      (node (ref "JP1") (pin "2") (pinfunction "2_2") (pintype "passive"))
      (node (ref "U$1") (pin "P18") (pinfunction "PB0_P18") (pintype "bidirectional"))
    )
    (net (code "43") (name "SWCLK") (class "Default")
      (node (ref "JP15") (pin "4") (pinfunction "4_4") (pintype "passive"))
      (node (ref "U$1") (pin "P37") (pinfunction "PA14_P37") (pintype "bidirectional"))
    )
    (net (code "44") (name "SWDIO") (class "Default")
      (node (ref "JP15") (pin "3") (pinfunction "3_3") (pintype "passive"))
      (node (ref "U$1") (pin "P34") (pinfunction "PA13_P34") (pintype "bidirectional"))
    )
    (net (code "45") (name "USB_DM") (class "Default")
      (node (ref "U$1") (pin "P32") (pinfunction "PA11_P32") (pintype "bidirectional"))
      (node (ref "U$3") (pin "P2") (pinfunction "DM_P2") (pintype "bidirectional"))
    )
    (net (code "46") (name "USB_DP") (class "Default")
      (node (ref "U$1") (pin "P33") (pinfunction "PA12_P33") (pintype "bidirectional"))
      (node (ref "U$3") (pin "P3") (pinfunction "DP_P3") (pintype "bidirectional"))
    )
    (net (code "47") (name "VUSB") (class "Default")
      (node (ref "C16") (pin "1") (pinfunction "1_1") (pintype "passive"))
      (node (ref "C22") (pin "1") (pinfunction "1_1") (pintype "passive"))
      (node (ref "C23") (pin "1") (pinfunction "1_1") (pintype "passive"))
      (node (ref "C24") (pin "1") (pinfunction "1_1") (pintype "passive"))
      (node (ref "C25") (pin "1") (pinfunction "1_1") (pintype "passive"))
      (node (ref "D2") (pin "2") (pinfunction "2_2") (pintype "bidirectional"))
      (node (ref "R19") (pin "1") (pinfunction "1_1") (pintype "passive"))
      (node (ref "U$2") (pin "2") (pinfunction "P2_2") (pintype "power_in"))
      (node (ref "U$4") (pin "2") (pinfunction "P2_2") (pintype "power_in"))
      (node (ref "U$5") (pin "2") (pinfunction "P2_2") (pintype "power_in"))
      (node (ref "U$6") (pin "2") (pinfunction "P2_2") (pintype "power_in"))
      (node (ref "U$7") (pin "P$1") (pinfunction "P$1_P$1") (pintype "bidirectional"))
      (node (ref "U$8") (pin "5") (pinfunction "VIN_5") (pintype "bidirectional"))
    )
    (net (code "48") (name "XBARDUAL_OUT") (class "Default")
      (node (ref "C6") (pin "1") (pinfunction "1_1") (pintype "passive"))
      (node (ref "R10") (pin "2") (pinfunction "2_2") (pintype "passive"))
      (node (ref "R9") (pin "2") (pinfunction "2_2") (pintype "passive"))
      (node (ref "U$5") (pin "3") (pinfunction "P3_3") (pintype "bidirectional"))
    )
    (net (code "49") (name "XCOARSE_IN") (class "Default")
      (node (ref "IC3") (pin "5") (pinfunction "I_5") (pintype "input"))
      (node (ref "R5") (pin "1") (pinfunction "1_1") (pintype "passive"))
      (node (ref "U$1") (pin "P38") (pinfunction "PA15_P38") (pintype "bidirectional"))
    )
    (net (code "50") (name "XDUAL_OUT") (class "Default")
      (node (ref "C4") (pin "1") (pinfunction "1_1") (pintype "passive"))
      (node (ref "R5") (pin "2") (pinfunction "2_2") (pintype "passive"))
      (node (ref "R6") (pin "2") (pinfunction "2_2") (pintype "passive"))
      (node (ref "U$2") (pin "3") (pinfunction "P3_3") (pintype "bidirectional"))
    )
    (net (code "51") (name "XFINE_IN") (class "Default")
      (node (ref "IC3") (pin "9") (pinfunction "I_9") (pintype "input"))
      (node (ref "R6") (pin "1") (pinfunction "1_1") (pintype "passive"))
      (node (ref "U$1") (pin "P39") (pinfunction "PB3_P39") (pintype "bidirectional"))
    )
    (net (code "52") (name "YBARDUAL_OUT") (class "Default")
      (node (ref "C7") (pin "1") (pinfunction "1_1") (pintype "passive"))
      (node (ref "R11") (pin "2") (pinfunction "2_2") (pintype "passive"))
      (node (ref "R12") (pin "2") (pinfunction "2_2") (pintype "passive"))
      (node (ref "U$6") (pin "3") (pinfunction "P3_3") (pintype "bidirectional"))
    )
    (net (code "53") (name "YCOARSE_IN") (class "Default")
      (node (ref "IC3") (pin "11") (pinfunction "I_11") (pintype "input"))
      (node (ref "R7") (pin "1") (pinfunction "1_1") (pintype "passive"))
      (node (ref "U$1") (pin "P21") (pinfunction "PB10_P21") (pintype "bidirectional"))
    )
    (net (code "54") (name "YDUAL_OUT") (class "Default")
      (node (ref "C5") (pin "1") (pinfunction "1_1") (pintype "passive"))
      (node (ref "R7") (pin "2") (pinfunction "2_2") (pintype "passive"))
      (node (ref "R8") (pin "2") (pinfunction "2_2") (pintype "passive"))
      (node (ref "U$4") (pin "3") (pinfunction "P3_3") (pintype "bidirectional"))
    )
    (net (code "55") (name "YFINE_IN") (class "Default")
      (node (ref "IC3") (pin "13") (pinfunction "I_13") (pintype "input"))
      (node (ref "R8") (pin "1") (pinfunction "1_1") (pintype "passive"))
      (node (ref "U$1") (pin "P22") (pinfunction "PB11_P22") (pintype "bidirectional"))
    )
    (net (code "56") (name "unconnected-(U$1-PA4-PadP14)") (class "Default")
      (node (ref "U$1") (pin "P14") (pinfunction "PA4_P14") (pintype "bidirectional"))
    )
    (net (code "57") (name "unconnected-(U$1-PA8-PadP29)") (class "Default")
      (node (ref "U$1") (pin "P29") (pinfunction "PA8_P29") (pintype "bidirectional"))
    )
    (net (code "58") (name "unconnected-(U$1-PA9-PadP30)") (class "Default")
      (node (ref "U$1") (pin "P30") (pinfunction "PA9_P30") (pintype "bidirectional"))
    )
    (net (code "59") (name "unconnected-(U$1-PA10-PadP31)") (class "Default")
      (node (ref "U$1") (pin "P31") (pinfunction "PA10_P31") (pintype "bidirectional"))
    )
    (net (code "60") (name "unconnected-(U$1-PB1-PadP19)") (class "Default")
      (node (ref "U$1") (pin "P19") (pinfunction "PB1_P19") (pintype "bidirectional"))
    )
    (net (code "61") (name "unconnected-(U$1-PB2-PadP20)") (class "Default")
      (node (ref "U$1") (pin "P20") (pinfunction "PB2_P20") (pintype "bidirectional"))
    )
    (net (code "62") (name "unconnected-(U$1-PB5-PadP41)") (class "Default")
      (node (ref "U$1") (pin "P41") (pinfunction "PB5_P41") (pintype "bidirectional"))
    )
    (net (code "63") (name "unconnected-(U$1-PB6-PadP42)") (class "Default")
      (node (ref "U$1") (pin "P42") (pinfunction "PB6_P42") (pintype "bidirectional"))
    )
    (net (code "64") (name "unconnected-(U$1-PB7-PadP43)") (class "Default")
      (node (ref "U$1") (pin "P43") (pinfunction "PB7_P43") (pintype "bidirectional"))
    )
    (net (code "65") (name "unconnected-(U$1-PB8-PadP45)") (class "Default")
      (node (ref "U$1") (pin "P45") (pinfunction "PB8_P45") (pintype "bidirectional"))
    )
    (net (code "66") (name "unconnected-(U$1-PB9-PadP46)") (class "Default")
      (node (ref "U$1") (pin "P46") (pinfunction "PB9_P46") (pintype "bidirectional"))
    )
    (net (code "67") (name "unconnected-(U$1-PB14-PadP27)") (class "Default")
      (node (ref "U$1") (pin "P27") (pinfunction "PB14_P27") (pintype "bidirectional"))
    )
    (net (code "68") (name "unconnected-(U$1-PB15-PadP28)") (class "Default")
      (node (ref "U$1") (pin "P28") (pinfunction "PB15_P28") (pintype "bidirectional"))
    )
    (net (code "69") (name "unconnected-(U$1-PC13-PadP2)") (class "Default")
      (node (ref "U$1") (pin "P2") (pinfunction "PC13_P2") (pintype "bidirectional"))
    )
    (net (code "70") (name "unconnected-(U$1-PC14-PadP3)") (class "Default")
      (node (ref "U$1") (pin "P3") (pinfunction "PC14_P3") (pintype "bidirectional"))
    )
    (net (code "71") (name "unconnected-(U$1-PC15-PadP4)") (class "Default")
      (node (ref "U$1") (pin "P4") (pinfunction "PC15_P4") (pintype "bidirectional"))
    )
  )
)
